# Ryu.net
KiCad netlist of a schematic drawn in Altium Designer
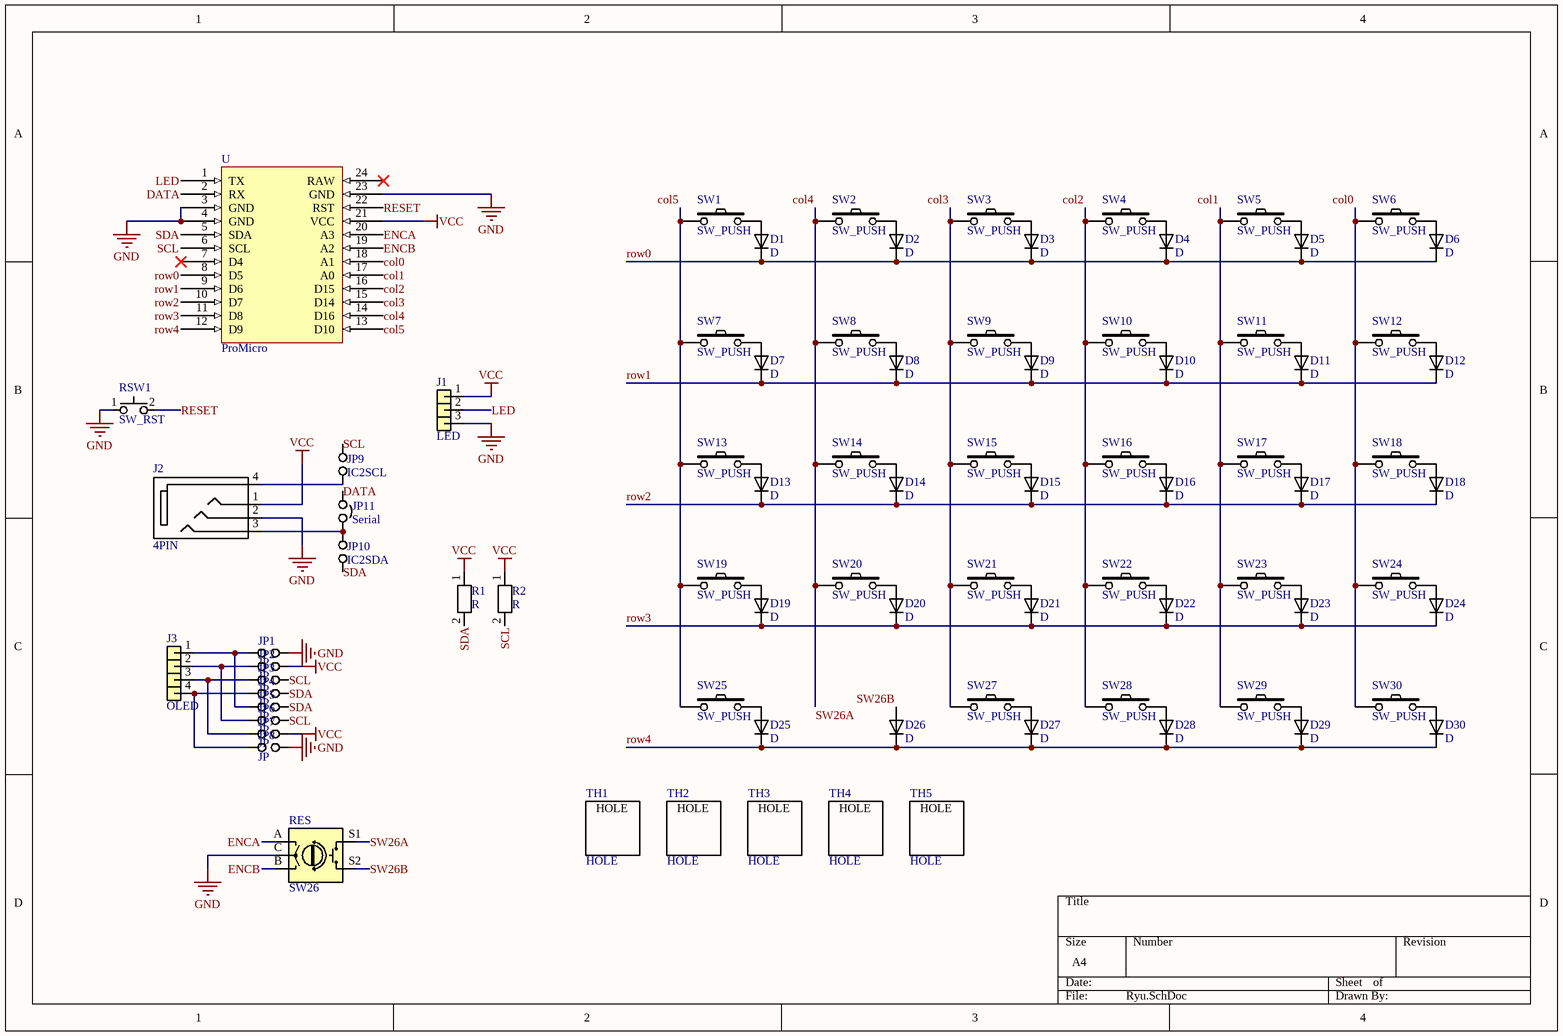
[diagram p0: Ryu.SchDoc]

(export (version "E")
  (design (tool "Eeschema 10.0.6"))
  (components
    (comp (ref "D1") (value "D") (footprint "D_SOD123") (libsource (lib "RyuSch") (part "D")))
    (comp (ref "D2") (value "D") (footprint "D_SOD123") (libsource (lib "RyuSch") (part "D")))
    (comp (ref "D3") (value "D") (footprint "D_SOD123") (libsource (lib "RyuSch") (part "D")))
    (comp (ref "D4") (value "D") (footprint "D_SOD123") (libsource (lib "RyuSch") (part "D")))
    (comp (ref "D5") (value "D") (footprint "D_SOD123") (libsource (lib "RyuSch") (part "D")))
    (comp (ref "D6") (value "D") (footprint "D_SOD123") (libsource (lib "RyuSch") (part "D")))
    (comp (ref "D7") (value "D") (footprint "D_SOD123") (libsource (lib "RyuSch") (part "D")))
    (comp (ref "D8") (value "D") (footprint "D_SOD123") (libsource (lib "RyuSch") (part "D")))
    (comp (ref "D9") (value "D") (footprint "D_SOD123") (libsource (lib "RyuSch") (part "D")))
    (comp (ref "D10") (value "D") (footprint "D_SOD123") (libsource (lib "RyuSch") (part "D")))
    (comp (ref "D11") (value "D") (footprint "D_SOD123") (libsource (lib "RyuSch") (part "D")))
    (comp (ref "D12") (value "D") (footprint "D_SOD123") (libsource (lib "RyuSch") (part "D")))
    (comp (ref "D13") (value "D") (footprint "D_SOD123") (libsource (lib "RyuSch") (part "D")))
    (comp (ref "D14") (value "D") (footprint "D_SOD123") (libsource (lib "RyuSch") (part "D")))
    (comp (ref "D15") (value "D") (footprint "D_SOD123") (libsource (lib "RyuSch") (part "D")))
    (comp (ref "D16") (value "D") (footprint "D_SOD123") (libsource (lib "RyuSch") (part "D")))
    (comp (ref "D17") (value "D") (footprint "D_SOD123") (libsource (lib "RyuSch") (part "D")))
    (comp (ref "D18") (value "D") (footprint "D_SOD123") (libsource (lib "RyuSch") (part "D")))
    (comp (ref "D19") (value "D") (footprint "D_SOD123") (libsource (lib "RyuSch") (part "D")))
    (comp (ref "D20") (value "D") (footprint "D_SOD123") (libsource (lib "RyuSch") (part "D")))
    (comp (ref "D21") (value "D") (footprint "D_SOD123") (libsource (lib "RyuSch") (part "D")))
    (comp (ref "D22") (value "D") (footprint "D_SOD123") (libsource (lib "RyuSch") (part "D")))
    (comp (ref "D23") (value "D") (footprint "D_SOD123") (libsource (lib "RyuSch") (part "D")))
    (comp (ref "D24") (value "D") (footprint "D_SOD123") (libsource (lib "RyuSch") (part "D")))
    (comp (ref "D25") (value "D") (footprint "D_SOD123") (libsource (lib "RyuSch") (part "D")))
    (comp (ref "D26") (value "D") (footprint "D_SOD123") (libsource (lib "RyuSch") (part "D")))
    (comp (ref "D27") (value "D") (footprint "D_SOD123") (libsource (lib "RyuSch") (part "D")))
    (comp (ref "D28") (value "D") (footprint "D_SOD123") (libsource (lib "RyuSch") (part "D")))
    (comp (ref "D29") (value "D") (footprint "D_SOD123") (libsource (lib "RyuSch") (part "D")))
    (comp (ref "D30") (value "D") (footprint "D_SOD123") (libsource (lib "RyuSch") (part "D")))
    (comp (ref "J1") (value "LED") (footprint "LED") (libsource (lib "RyuSch") (part "LED")))
    (comp (ref "J2") (value "4PIN") (footprint "TRRS") (libsource (lib "RyuSch") (part "4PIN")))
    (comp (ref "J3") (value "OLED") (footprint "OLED") (libsource (lib "RyuSch") (part "OLED")))
    (comp (ref "JP1") (value "JP") (footprint "JUMPER") (libsource (lib "RyuSch") (part "JP")))
    (comp (ref "JP2") (value "JP") (footprint "JUMPER") (libsource (lib "RyuSch") (part "JP")))
    (comp (ref "JP3") (value "JP") (footprint "JUMPER") (libsource (lib "RyuSch") (part "JP")))
    (comp (ref "JP4") (value "JP") (footprint "JUMPER") (libsource (lib "RyuSch") (part "JP")))
    (comp (ref "JP5") (value "JP") (footprint "JUMPER") (libsource (lib "RyuSch") (part "JP")))
    (comp (ref "JP6") (value "JP") (footprint "JUMPER") (libsource (lib "RyuSch") (part "JP")))
    (comp (ref "JP7") (value "JP") (footprint "JUMPER") (libsource (lib "RyuSch") (part "JP")))
    (comp (ref "JP8") (value "JP") (footprint "JUMPER") (libsource (lib "RyuSch") (part "JP")))
    (comp (ref "JP9") (value "IC2SCL") (footprint "JUMPER_Triangle") (libsource (lib "RyuSch") (part "JP")))
    (comp (ref "JP10") (value "IC2SDA") (footprint "JUMPER_Triangle") (libsource (lib "RyuSch") (part "JP")))
    (comp (ref "JP11") (value "Serial") (footprint "JUMPER_DATA") (libsource (lib "RyuSch") (part "JP_C")))
    (comp (ref "R1") (value "R") (footprint "RESISTOR") (libsource (lib "RyuSch") (part "R")))
    (comp (ref "R2") (value "R") (footprint "RESISTOR") (libsource (lib "RyuSch") (part "R")))
    (comp (ref "RES") (value "SW26") (footprint "Rotary_Encoder_Alps") (libsource (lib "RyuSch") (part "SW")))
    (comp (ref "RSW1") (value "SW_RST") (footprint "RST_SWITCH") (libsource (lib "RyuSch") (part "SW_RST")))
    (comp (ref "SW1")
      (value "SW_PUSH")
      (footprint "1u-CherryMX-Hotswap-Dualside")
      (libsource (lib "RyuSch") (part "SW_PUSH"))
    )
    (comp (ref "SW2")
      (value "SW_PUSH")
      (footprint "1u-CherryMX-Hotswap-Dualside")
      (libsource (lib "RyuSch") (part "SW_PUSH"))
    )
    (comp (ref "SW3")
      (value "SW_PUSH")
      (footprint "1u-CherryMX-Hotswap-Dualside")
      (libsource (lib "RyuSch") (part "SW_PUSH"))
    )
    (comp (ref "SW4")
      (value "SW_PUSH")
      (footprint "1u-CherryMX-Hotswap-Dualside")
      (libsource (lib "RyuSch") (part "SW_PUSH"))
    )
    (comp (ref "SW5")
      (value "SW_PUSH")
      (footprint "1u-CherryMX-Hotswap-Dualside")
      (libsource (lib "RyuSch") (part "SW_PUSH"))
    )
    (comp (ref "SW6")
      (value "SW_PUSH")
      (footprint "1.5u-CHERRYmx-hotswap-dualside")
      (libsource (lib "RyuSch") (part "SW_PUSH"))
    )
    (comp (ref "SW7")
      (value "SW_PUSH")
      (footprint "1u-CherryMX-Hotswap-Dualside")
      (libsource (lib "RyuSch") (part "SW_PUSH"))
    )
    (comp (ref "SW8")
      (value "SW_PUSH")
      (footprint "1u-CherryMX-Hotswap-Dualside")
      (libsource (lib "RyuSch") (part "SW_PUSH"))
    )
    (comp (ref "SW9")
      (value "SW_PUSH")
      (footprint "1u-CherryMX-Hotswap-Dualside")
      (libsource (lib "RyuSch") (part "SW_PUSH"))
    )
    (comp (ref "SW10")
      (value "SW_PUSH")
      (footprint "1u-CherryMX-Hotswap-Dualside")
      (libsource (lib "RyuSch") (part "SW_PUSH"))
    )
    (comp (ref "SW11")
      (value "SW_PUSH")
      (footprint "1u-CherryMX-Hotswap-Dualside")
      (libsource (lib "RyuSch") (part "SW_PUSH"))
    )
    (comp (ref "SW12")
      (value "SW_PUSH")
      (footprint "1.5u-CHERRYmx-hotswap-dualside")
      (libsource (lib "RyuSch") (part "SW_PUSH"))
    )
    (comp (ref "SW13")
      (value "SW_PUSH")
      (footprint "1u-CherryMX-Hotswap-Dualside")
      (libsource (lib "RyuSch") (part "SW_PUSH"))
    )
    (comp (ref "SW14")
      (value "SW_PUSH")
      (footprint "1u-CherryMX-Hotswap-Dualside")
      (libsource (lib "RyuSch") (part "SW_PUSH"))
    )
    (comp (ref "SW15")
      (value "SW_PUSH")
      (footprint "1u-CherryMX-Hotswap-Dualside")
      (libsource (lib "RyuSch") (part "SW_PUSH"))
    )
    (comp (ref "SW16")
      (value "SW_PUSH")
      (footprint "1u-CherryMX-Hotswap-Dualside")
      (libsource (lib "RyuSch") (part "SW_PUSH"))
    )
    (comp (ref "SW17")
      (value "SW_PUSH")
      (footprint "1u-CherryMX-Hotswap-Dualside")
      (libsource (lib "RyuSch") (part "SW_PUSH"))
    )
    (comp (ref "SW18")
      (value "SW_PUSH")
      (footprint "1.5u-CHERRYmx-hotswap-dualside")
      (libsource (lib "RyuSch") (part "SW_PUSH"))
    )
    (comp (ref "SW19")
      (value "SW_PUSH")
      (footprint "1u-CherryMX-Hotswap-Dualside")
      (libsource (lib "RyuSch") (part "SW_PUSH"))
    )
    (comp (ref "SW20")
      (value "SW_PUSH")
      (footprint "1u-CherryMX-Hotswap-Dualside")
      (libsource (lib "RyuSch") (part "SW_PUSH"))
    )
    (comp (ref "SW21")
      (value "SW_PUSH")
      (footprint "1u-CherryMX-Hotswap-Dualside")
      (libsource (lib "RyuSch") (part "SW_PUSH"))
    )
    (comp (ref "SW22")
      (value "SW_PUSH")
      (footprint "1u-CherryMX-Hotswap-Dualside")
      (libsource (lib "RyuSch") (part "SW_PUSH"))
    )
    (comp (ref "SW23")
      (value "SW_PUSH")
      (footprint "1u-CherryMX-Hotswap-Dualside")
      (libsource (lib "RyuSch") (part "SW_PUSH"))
    )
    (comp (ref "SW24")
      (value "SW_PUSH")
      (footprint "1.5u-CHERRYmx-hotswap-dualside")
      (libsource (lib "RyuSch") (part "SW_PUSH"))
    )
    (comp (ref "SW25")
      (value "SW_PUSH")
      (footprint "1u-CherryMX-Hotswap-Dualside")
      (libsource (lib "RyuSch") (part "SW_PUSH"))
    )
    (comp (ref "SW27")
      (value "SW_PUSH")
      (footprint "1.5u-CHERRYmx-hotswap-dualside")
      (libsource (lib "RyuSch") (part "SW_PUSH"))
    )
    (comp (ref "SW28")
      (value "SW_PUSH")
      (footprint "1u-CherryMX-Hotswap-Dualside")
      (libsource (lib "RyuSch") (part "SW_PUSH"))
    )
    (comp (ref "SW29")
      (value "SW_PUSH")
      (footprint "1u-CherryMX-Hotswap-Dualside")
      (libsource (lib "RyuSch") (part "SW_PUSH"))
    )
    (comp (ref "SW30")
      (value "SW_PUSH")
      (footprint "1u-CherryMX-Hotswap-Dualside")
      (libsource (lib "RyuSch") (part "SW_PUSH"))
    )
    (comp (ref "TH1") (value "HOLE") (footprint "M2_TH_HOLE") (libsource (lib "RyuSch") (part "HOLE")))
    (comp (ref "TH2") (value "HOLE") (footprint "M2_TH_HOLE") (libsource (lib "RyuSch") (part "HOLE")))
    (comp (ref "TH3") (value "HOLE") (footprint "M2_TH_HOLE") (libsource (lib "RyuSch") (part "HOLE")))
    (comp (ref "TH4") (value "HOLE") (footprint "M2_TH_HOLE") (libsource (lib "RyuSch") (part "HOLE")))
    (comp (ref "TH5") (value "HOLE") (footprint "M2_TH_HOLE") (libsource (lib "RyuSch") (part "HOLE")))
    (comp (ref "U") (value "ProMicro") (footprint "ProMicro") (libsource (lib "RyuSch") (part "ProMicro")))
  )
  (nets
    (net (code "1") (name "/DATA") (class "Default")
      (node (ref "JP11") (pin "J1") (pinfunction "28_J1") (pintype "passive"))
      (node (ref "U") (pin "2") (pinfunction "RX_2") (pintype "input"))
    )
    (net (code "2") (name "/ENCA") (class "Default")
      (node (ref "RES") (pin "A") (pinfunction "A_A") (pintype "passive"))
      (node (ref "U") (pin "20") (pinfunction "A3_20") (pintype "input"))
    )
    (net (code "3") (name "/ENCB") (class "Default")
      (node (ref "RES") (pin "B") (pinfunction "C_B") (pintype "passive"))
      (node (ref "U") (pin "19") (pinfunction "A2_19") (pintype "input"))
    )
    (net (code "4") (name "/LED") (class "Default")
      (node (ref "J1") (pin "2") (pinfunction "16_2") (pintype "passive"))
      (node (ref "U") (pin "1") (pinfunction "TX_1") (pintype "input"))
    )
    (net (code "5") (name "/RESET") (class "Default")
      (node (ref "RSW1") (pin "2") (pinfunction "12_2") (pintype "passive"))
      (node (ref "U") (pin "22") (pinfunction "RST_22") (pintype "input"))
    )
    (net (code "6") (name "/SCL") (class "Default")
      (node (ref "JP3") (pin "J2") (pinfunction "27_J2") (pintype "passive"))
      (node (ref "JP6") (pin "J2") (pinfunction "27_J2") (pintype "passive"))
      (node (ref "JP9") (pin "J2") (pinfunction "27_J2") (pintype "passive"))
      (node (ref "R2") (pin "2") (pinfunction "5_2") (pintype "passive"))
      (node (ref "U") (pin "6") (pinfunction "SCL_6") (pintype "input"))
    )
    (net (code "7") (name "/SDA") (class "Default")
      (node (ref "JP10") (pin "J2") (pinfunction "27_J2") (pintype "passive"))
      (node (ref "JP4") (pin "J2") (pinfunction "27_J2") (pintype "passive"))
      (node (ref "JP5") (pin "J2") (pinfunction "27_J2") (pintype "passive"))
      (node (ref "R1") (pin "2") (pinfunction "5_2") (pintype "passive"))
      (node (ref "U") (pin "5") (pinfunction "SDA_5") (pintype "input"))
    )
    (net (code "8") (name "/SW26A") (class "Default")
      (node (ref "RES") (pin "S1") (pinfunction "8_S1") (pintype "passive"))
      (node (ref "SW14") (pin "1") (pinfunction "1_1") (pintype "passive"))
      (node (ref "SW2") (pin "1") (pinfunction "1_1") (pintype "passive"))
      (node (ref "SW20") (pin "1") (pinfunction "1_1") (pintype "passive"))
      (node (ref "SW8") (pin "1") (pinfunction "1_1") (pintype "passive"))
      (node (ref "U") (pin "14") (pinfunction "D16_14") (pintype "input"))
    )
    (net (code "9") (name "/SW26B") (class "Default")
      (node (ref "D26") (pin "2") (pinfunction "A_2") (pintype "passive"))
      (node (ref "RES") (pin "S2") (pinfunction "9_S2") (pintype "passive"))
    )
    (net (code "10") (name "/col0") (class "Default")
      (node (ref "SW12") (pin "1") (pinfunction "1_1") (pintype "passive"))
      (node (ref "SW18") (pin "1") (pinfunction "1_1") (pintype "passive"))
      (node (ref "SW24") (pin "1") (pinfunction "1_1") (pintype "passive"))
      (node (ref "SW30") (pin "1") (pinfunction "1_1") (pintype "passive"))
      (node (ref "SW6") (pin "1") (pinfunction "1_1") (pintype "passive"))
      (node (ref "U") (pin "18") (pinfunction "A1_18") (pintype "input"))
    )
    (net (code "11") (name "/col1") (class "Default")
      (node (ref "SW11") (pin "1") (pinfunction "1_1") (pintype "passive"))
      (node (ref "SW17") (pin "1") (pinfunction "1_1") (pintype "passive"))
      (node (ref "SW23") (pin "1") (pinfunction "1_1") (pintype "passive"))
      (node (ref "SW29") (pin "1") (pinfunction "1_1") (pintype "passive"))
      (node (ref "SW5") (pin "1") (pinfunction "1_1") (pintype "passive"))
      (node (ref "U") (pin "17") (pinfunction "A0_17") (pintype "input"))
    )
    (net (code "12") (name "/col2") (class "Default")
      (node (ref "SW10") (pin "1") (pinfunction "1_1") (pintype "passive"))
      (node (ref "SW16") (pin "1") (pinfunction "1_1") (pintype "passive"))
      (node (ref "SW22") (pin "1") (pinfunction "1_1") (pintype "passive"))
      (node (ref "SW28") (pin "1") (pinfunction "1_1") (pintype "passive"))
      (node (ref "SW4") (pin "1") (pinfunction "1_1") (pintype "passive"))
      (node (ref "U") (pin "16") (pinfunction "D15_16") (pintype "input"))
    )
    (net (code "13") (name "/col3") (class "Default")
      (node (ref "SW15") (pin "1") (pinfunction "1_1") (pintype "passive"))
      (node (ref "SW21") (pin "1") (pinfunction "1_1") (pintype "passive"))
      (node (ref "SW27") (pin "1") (pinfunction "1_1") (pintype "passive"))
      (node (ref "SW3") (pin "1") (pinfunction "1_1") (pintype "passive"))
      (node (ref "SW9") (pin "1") (pinfunction "1_1") (pintype "passive"))
      (node (ref "U") (pin "15") (pinfunction "D14_15") (pintype "input"))
    )
    (net (code "14") (name "/col5") (class "Default")
      (node (ref "SW1") (pin "1") (pinfunction "1_1") (pintype "passive"))
      (node (ref "SW13") (pin "1") (pinfunction "1_1") (pintype "passive"))
      (node (ref "SW19") (pin "1") (pinfunction "1_1") (pintype "passive"))
      (node (ref "SW25") (pin "1") (pinfunction "1_1") (pintype "passive"))
      (node (ref "SW7") (pin "1") (pinfunction "1_1") (pintype "passive"))
      (node (ref "U") (pin "13") (pinfunction "D10_13") (pintype "input"))
    )
    (net (code "15") (name "/row0") (class "Default")
      (node (ref "D1") (pin "1") (pinfunction "K_1") (pintype "passive"))
      (node (ref "D2") (pin "1") (pinfunction "K_1") (pintype "passive"))
      (node (ref "D3") (pin "1") (pinfunction "K_1") (pintype "passive"))
      (node (ref "D4") (pin "1") (pinfunction "K_1") (pintype "passive"))
      (node (ref "D5") (pin "1") (pinfunction "K_1") (pintype "passive"))
      (node (ref "D6") (pin "1") (pinfunction "K_1") (pintype "passive"))
      (node (ref "U") (pin "8") (pinfunction "D5_8") (pintype "input"))
    )
    (net (code "16") (name "/row1") (class "Default")
      (node (ref "D10") (pin "1") (pinfunction "K_1") (pintype "passive"))
      (node (ref "D11") (pin "1") (pinfunction "K_1") (pintype "passive"))
      (node (ref "D12") (pin "1") (pinfunction "K_1") (pintype "passive"))
      (node (ref "D7") (pin "1") (pinfunction "K_1") (pintype "passive"))
      (node (ref "D8") (pin "1") (pinfunction "K_1") (pintype "passive"))
      (node (ref "D9") (pin "1") (pinfunction "K_1") (pintype "passive"))
      (node (ref "U") (pin "9") (pinfunction "D6_9") (pintype "input"))
    )
    (net (code "17") (name "/row2") (class "Default")
      (node (ref "D13") (pin "1") (pinfunction "K_1") (pintype "passive"))
      (node (ref "D14") (pin "1") (pinfunction "K_1") (pintype "passive"))
      (node (ref "D15") (pin "1") (pinfunction "K_1") (pintype "passive"))
      (node (ref "D16") (pin "1") (pinfunction "K_1") (pintype "passive"))
      (node (ref "D17") (pin "1") (pinfunction "K_1") (pintype "passive"))
      (node (ref "D18") (pin "1") (pinfunction "K_1") (pintype "passive"))
      (node (ref "U") (pin "10") (pinfunction "D7_10") (pintype "input"))
    )
    (net (code "18") (name "/row3") (class "Default")
      (node (ref "D19") (pin "1") (pinfunction "K_1") (pintype "passive"))
      (node (ref "D20") (pin "1") (pinfunction "K_1") (pintype "passive"))
      (node (ref "D21") (pin "1") (pinfunction "K_1") (pintype "passive"))
      (node (ref "D22") (pin "1") (pinfunction "K_1") (pintype "passive"))
      (node (ref "D23") (pin "1") (pinfunction "K_1") (pintype "passive"))
      (node (ref "D24") (pin "1") (pinfunction "K_1") (pintype "passive"))
      (node (ref "U") (pin "11") (pinfunction "D8_11") (pintype "input"))
    )
    (net (code "19") (name "/row4") (class "Default")
      (node (ref "D25") (pin "1") (pinfunction "K_1") (pintype "passive"))
      (node (ref "D26") (pin "1") (pinfunction "K_1") (pintype "passive"))
      (node (ref "D27") (pin "1") (pinfunction "K_1") (pintype "passive"))
      (node (ref "D28") (pin "1") (pinfunction "K_1") (pintype "passive"))
      (node (ref "D29") (pin "1") (pinfunction "K_1") (pintype "passive"))
      (node (ref "D30") (pin "1") (pinfunction "K_1") (pintype "passive"))
      (node (ref "U") (pin "12") (pinfunction "D9_12") (pintype "input"))
    )
    (net (code "20") (name "GND") (class "Default")
      (node (ref "J1") (pin "3") (pinfunction "17_3") (pintype "passive"))
      (node (ref "J2") (pin "2") (pinfunction "21_2") (pintype "passive"))
      (node (ref "JP1") (pin "J2") (pinfunction "27_J2") (pintype "passive"))
      (node (ref "JP8") (pin "J2") (pinfunction "27_J2") (pintype "passive"))
      (node (ref "RES") (pin "C") (pinfunction "B_C") (pintype "passive"))
      (node (ref "RSW1") (pin "1") (pinfunction "13_1") (pintype "passive"))
      (node (ref "U") (pin "23") (pinfunction "GND_23") (pintype "input"))
      (node (ref "U") (pin "3") (pinfunction "GND_3") (pintype "input"))
      (node (ref "U") (pin "4") (pinfunction "GND_4") (pintype "input"))
    )
    (net (code "21") (name "Net-(D1-A)") (class "Default")
      (node (ref "D1") (pin "2") (pinfunction "A_2") (pintype "passive"))
      (node (ref "SW1") (pin "2") (pinfunction "2_2") (pintype "passive"))
    )
    (net (code "22") (name "Net-(D2-A)") (class "Default")
      (node (ref "D2") (pin "2") (pinfunction "A_2") (pintype "passive"))
      (node (ref "SW2") (pin "2") (pinfunction "2_2") (pintype "passive"))
    )
    (net (code "23") (name "Net-(D3-A)") (class "Default")
      (node (ref "D3") (pin "2") (pinfunction "A_2") (pintype "passive"))
      (node (ref "SW3") (pin "2") (pinfunction "2_2") (pintype "passive"))
    )
    (net (code "24") (name "Net-(D4-A)") (class "Default")
      (node (ref "D4") (pin "2") (pinfunction "A_2") (pintype "passive"))
      (node (ref "SW4") (pin "2") (pinfunction "2_2") (pintype "passive"))
    )
    (net (code "25") (name "Net-(D5-A)") (class "Default")
      (node (ref "D5") (pin "2") (pinfunction "A_2") (pintype "passive"))
      (node (ref "SW5") (pin "2") (pinfunction "2_2") (pintype "passive"))
    )
    (net (code "26") (name "Net-(D6-A)") (class "Default")
      (node (ref "D6") (pin "2") (pinfunction "A_2") (pintype "passive"))
      (node (ref "SW6") (pin "2") (pinfunction "2_2") (pintype "passive"))
    )
    (net (code "27") (name "Net-(D7-A)") (class "Default")
      (node (ref "D7") (pin "2") (pinfunction "A_2") (pintype "passive"))
      (node (ref "SW7") (pin "2") (pinfunction "2_2") (pintype "passive"))
    )
    (net (code "28") (name "Net-(D8-A)") (class "Default")
      (node (ref "D8") (pin "2") (pinfunction "A_2") (pintype "passive"))
      (node (ref "SW8") (pin "2") (pinfunction "2_2") (pintype "passive"))
    )
    (net (code "29") (name "Net-(D9-A)") (class "Default")
      (node (ref "D9") (pin "2") (pinfunction "A_2") (pintype "passive"))
      (node (ref "SW9") (pin "2") (pinfunction "2_2") (pintype "passive"))
    )
    (net (code "30") (name "Net-(D10-A)") (class "Default")
      (node (ref "D10") (pin "2") (pinfunction "A_2") (pintype "passive"))
      (node (ref "SW10") (pin "2") (pinfunction "2_2") (pintype "passive"))
    )
    (net (code "31") (name "Net-(D11-A)") (class "Default")
      (node (ref "D11") (pin "2") (pinfunction "A_2") (pintype "passive"))
      (node (ref "SW11") (pin "2") (pinfunction "2_2") (pintype "passive"))
    )
    (net (code "32") (name "Net-(D12-A)") (class "Default")
      (node (ref "D12") (pin "2") (pinfunction "A_2") (pintype "passive"))
      (node (ref "SW12") (pin "2") (pinfunction "2_2") (pintype "passive"))
    )
    (net (code "33") (name "Net-(D13-A)") (class "Default")
      (node (ref "D13") (pin "2") (pinfunction "A_2") (pintype "passive"))
      (node (ref "SW13") (pin "2") (pinfunction "2_2") (pintype "passive"))
    )
    (net (code "34") (name "Net-(D14-A)") (class "Default")
      (node (ref "D14") (pin "2") (pinfunction "A_2") (pintype "passive"))
      (node (ref "SW14") (pin "2") (pinfunction "2_2") (pintype "passive"))
    )
    (net (code "35") (name "Net-(D15-A)") (class "Default")
      (node (ref "D15") (pin "2") (pinfunction "A_2") (pintype "passive"))
      (node (ref "SW15") (pin "2") (pinfunction "2_2") (pintype "passive"))
    )
    (net (code "36") (name "Net-(D16-A)") (class "Default")
      (node (ref "D16") (pin "2") (pinfunction "A_2") (pintype "passive"))
      (node (ref "SW16") (pin "2") (pinfunction "2_2") (pintype "passive"))
    )
    (net (code "37") (name "Net-(D17-A)") (class "Default")
      (node (ref "D17") (pin "2") (pinfunction "A_2") (pintype "passive"))
      (node (ref "SW17") (pin "2") (pinfunction "2_2") (pintype "passive"))
    )
    (net (code "38") (name "Net-(D18-A)") (class "Default")
      (node (ref "D18") (pin "2") (pinfunction "A_2") (pintype "passive"))
      (node (ref "SW18") (pin "2") (pinfunction "2_2") (pintype "passive"))
    )
    (net (code "39") (name "Net-(D19-A)") (class "Default")
      (node (ref "D19") (pin "2") (pinfunction "A_2") (pintype "passive"))
      (node (ref "SW19") (pin "2") (pinfunction "2_2") (pintype "passive"))
    )
    (net (code "40") (name "Net-(D20-A)") (class "Default")
      (node (ref "D20") (pin "2") (pinfunction "A_2") (pintype "passive"))
      (node (ref "SW20") (pin "2") (pinfunction "2_2") (pintype "passive"))
    )
    (net (code "41") (name "Net-(D21-A)") (class "Default")
      (node (ref "D21") (pin "2") (pinfunction "A_2") (pintype "passive"))
      (node (ref "SW21") (pin "2") (pinfunction "2_2") (pintype "passive"))
    )
    (net (code "42") (name "Net-(D22-A)") (class "Default")
      (node (ref "D22") (pin "2") (pinfunction "A_2") (pintype "passive"))
      (node (ref "SW22") (pin "2") (pinfunction "2_2") (pintype "passive"))
    )
    (net (code "43") (name "Net-(D23-A)") (class "Default")
      (node (ref "D23") (pin "2") (pinfunction "A_2") (pintype "passive"))
      (node (ref "SW23") (pin "2") (pinfunction "2_2") (pintype "passive"))
    )
    (net (code "44") (name "Net-(D24-A)") (class "Default")
      (node (ref "D24") (pin "2") (pinfunction "A_2") (pintype "passive"))
      (node (ref "SW24") (pin "2") (pinfunction "2_2") (pintype "passive"))
    )
    (net (code "45") (name "Net-(D25-A)") (class "Default")
      (node (ref "D25") (pin "2") (pinfunction "A_2") (pintype "passive"))
      (node (ref "SW25") (pin "2") (pinfunction "2_2") (pintype "passive"))
    )
    (net (code "46") (name "Net-(D27-A)") (class "Default")
      (node (ref "D27") (pin "2") (pinfunction "A_2") (pintype "passive"))
      (node (ref "SW27") (pin "2") (pinfunction "2_2") (pintype "passive"))
    )
    (net (code "47") (name "Net-(D28-A)") (class "Default")
      (node (ref "D28") (pin "2") (pinfunction "A_2") (pintype "passive"))
      (node (ref "SW28") (pin "2") (pinfunction "2_2") (pintype "passive"))
    )
    (net (code "48") (name "Net-(D29-A)") (class "Default")
      (node (ref "D29") (pin "2") (pinfunction "A_2") (pintype "passive"))
      (node (ref "SW29") (pin "2") (pinfunction "2_2") (pintype "passive"))
    )
    (net (code "49") (name "Net-(D30-A)") (class "Default")
      (node (ref "D30") (pin "2") (pinfunction "A_2") (pintype "passive"))
      (node (ref "SW30") (pin "2") (pinfunction "2_2") (pintype "passive"))
    )
    (net (code "50") (name "Net-(J2-19)") (class "Default")
      (node (ref "J2") (pin "4") (pinfunction "19_4") (pintype "passive"))
      (node (ref "JP9") (pin "J1") (pinfunction "28_J1") (pintype "passive"))
    )
    (net (code "51") (name "Net-(J2-22)") (class "Default")
      (node (ref "J2") (pin "3") (pinfunction "22_3") (pintype "passive"))
      (node (ref "JP10") (pin "J1") (pinfunction "28_J1") (pintype "passive"))
      (node (ref "JP11") (pin "J2") (pinfunction "27_J2") (pintype "passive"))
    )
    (net (code "52") (name "Net-(JP1-28)") (class "Default")
      (node (ref "J3") (pin "1") (pintype "passive"))
      (node (ref "JP1") (pin "J1") (pinfunction "28_J1") (pintype "passive"))
      (node (ref "JP5") (pin "J1") (pinfunction "28_J1") (pintype "passive"))
    )
    (net (code "53") (name "Net-(JP2-28)") (class "Default")
      (node (ref "J3") (pin "2") (pintype "passive"))
      (node (ref "JP2") (pin "J1") (pinfunction "28_J1") (pintype "passive"))
      (node (ref "JP6") (pin "J1") (pinfunction "28_J1") (pintype "passive"))
    )
    (net (code "54") (name "Net-(JP3-28)") (class "Default")
      (node (ref "J3") (pin "3") (pintype "passive"))
      (node (ref "JP3") (pin "J1") (pinfunction "28_J1") (pintype "passive"))
      (node (ref "JP7") (pin "J1") (pinfunction "28_J1") (pintype "passive"))
    )
    (net (code "55") (name "Net-(JP4-28)") (class "Default")
      (node (ref "J3") (pin "4") (pintype "passive"))
      (node (ref "JP4") (pin "J1") (pinfunction "28_J1") (pintype "passive"))
      (node (ref "JP8") (pin "J1") (pinfunction "28_J1") (pintype "passive"))
    )
    (net (code "56") (name "VCC") (class "Default")
      (node (ref "J1") (pin "1") (pinfunction "15_1") (pintype "passive"))
      (node (ref "J2") (pin "1") (pinfunction "20_1") (pintype "passive"))
      (node (ref "JP2") (pin "J2") (pinfunction "27_J2") (pintype "passive"))
      (node (ref "JP7") (pin "J2") (pinfunction "27_J2") (pintype "passive"))
      (node (ref "R1") (pin "1") (pinfunction "11_1") (pintype "passive"))
      (node (ref "R2") (pin "1") (pinfunction "11_1") (pintype "passive"))
      (node (ref "U") (pin "21") (pinfunction "VCC_21") (pintype "input"))
    )
    (net (code "57") (name "unconnected-(U-D4-Pad7)") (class "Default")
      (node (ref "U") (pin "7") (pinfunction "D4_7") (pintype "input+no_connect"))
    )
    (net (code "58") (name "unconnected-(U-RAW-Pad24)") (class "Default")
      (node (ref "U") (pin "24") (pinfunction "RAW_24") (pintype "input+no_connect"))
    )
  )
)
